# sub-unit-psu.net
KiCad netlist of a schematic drawn in EAGLE
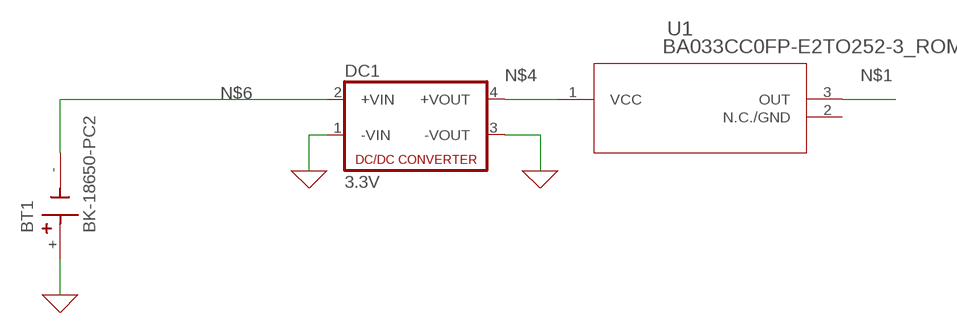
[diagram p0: schematic, sheet 1]

(export (version "E")
  (design (tool "Eeschema 10.0.6"))
  (components
    (comp (ref "BT1")
      (value "BK-18650-PC2")
      (footprint "eagle-import:BAT_BK-18650-PC2")
      (fields (field (name "MF") "MPD (Memory Protection Devices)"))
      (libsource (lib "eagle-import") (part "BK-18650-PC2"))
    )
    (comp (ref "DC1")
      (value "3.3V")
      (footprint "eagle-import:NME")
      (fields (field (name "MF") "C & D TECHNOLOGIES, INC") (field (name "MPN") "NME1205D"))
      (libsource (lib "eagle-import") (part "NME"))
    )
    (comp (ref "U1")
      (value "BA033CC0FP-E2TO252-3_ROM")
      (footprint "eagle-import:TO252-3_ROM")
      (fields
        (field (name "MANUFACTURER_PART_NUMBER") "BA033CC0FP-E2")
        (field (name "COPYRIGHT") "Copyright (C) 2023 Ultra Librarian. All rights reserved.")
      )
      (libsource (lib "eagle-import") (part "BA033CC0FP-E2TO252-3_ROM"))
    )
  )
  (nets
    (net (code "1") (name "/N$1") (class "Default")
      (node (ref "U1") (pin "3") (pinfunction "OUT_3") (pintype "output"))
    )
    (net (code "2") (name "/N$4") (class "Default")
      (node (ref "DC1") (pin "4") (pinfunction "+VOUT_4") (pintype "passive"))
      (node (ref "U1") (pin "1") (pinfunction "VCC_1") (pintype "power_in"))
    )
    (net (code "3") (name "/N$6") (class "Default")
      (node (ref "BT1") (pin "-") (pinfunction "-_-") (pintype "passive"))
      (node (ref "DC1") (pin "2") (pinfunction "+VIN_2") (pintype "passive"))
    )
    (net (code "4") (name "GND") (class "Default")
      (node (ref "BT1") (pin "+") (pinfunction "+_+") (pintype "passive"))
      (node (ref "DC1") (pin "1") (pinfunction "-VIN_1") (pintype "passive"))
      (node (ref "DC1") (pin "3") (pinfunction "-VOUT_3") (pintype "passive"))
    )
    (net (code "5") (name "unconnected-(U1-N.C.{slash}GND-Pad2)") (class "Default")
      (node (ref "U1") (pin "2") (pinfunction "N.C./GND_2") (pintype "no_connect"))
    )
  )
)
